# TTAmp_3T0K_amp_tensometer_3.net
KiCad netlist of a schematic drawn in Altium Designer
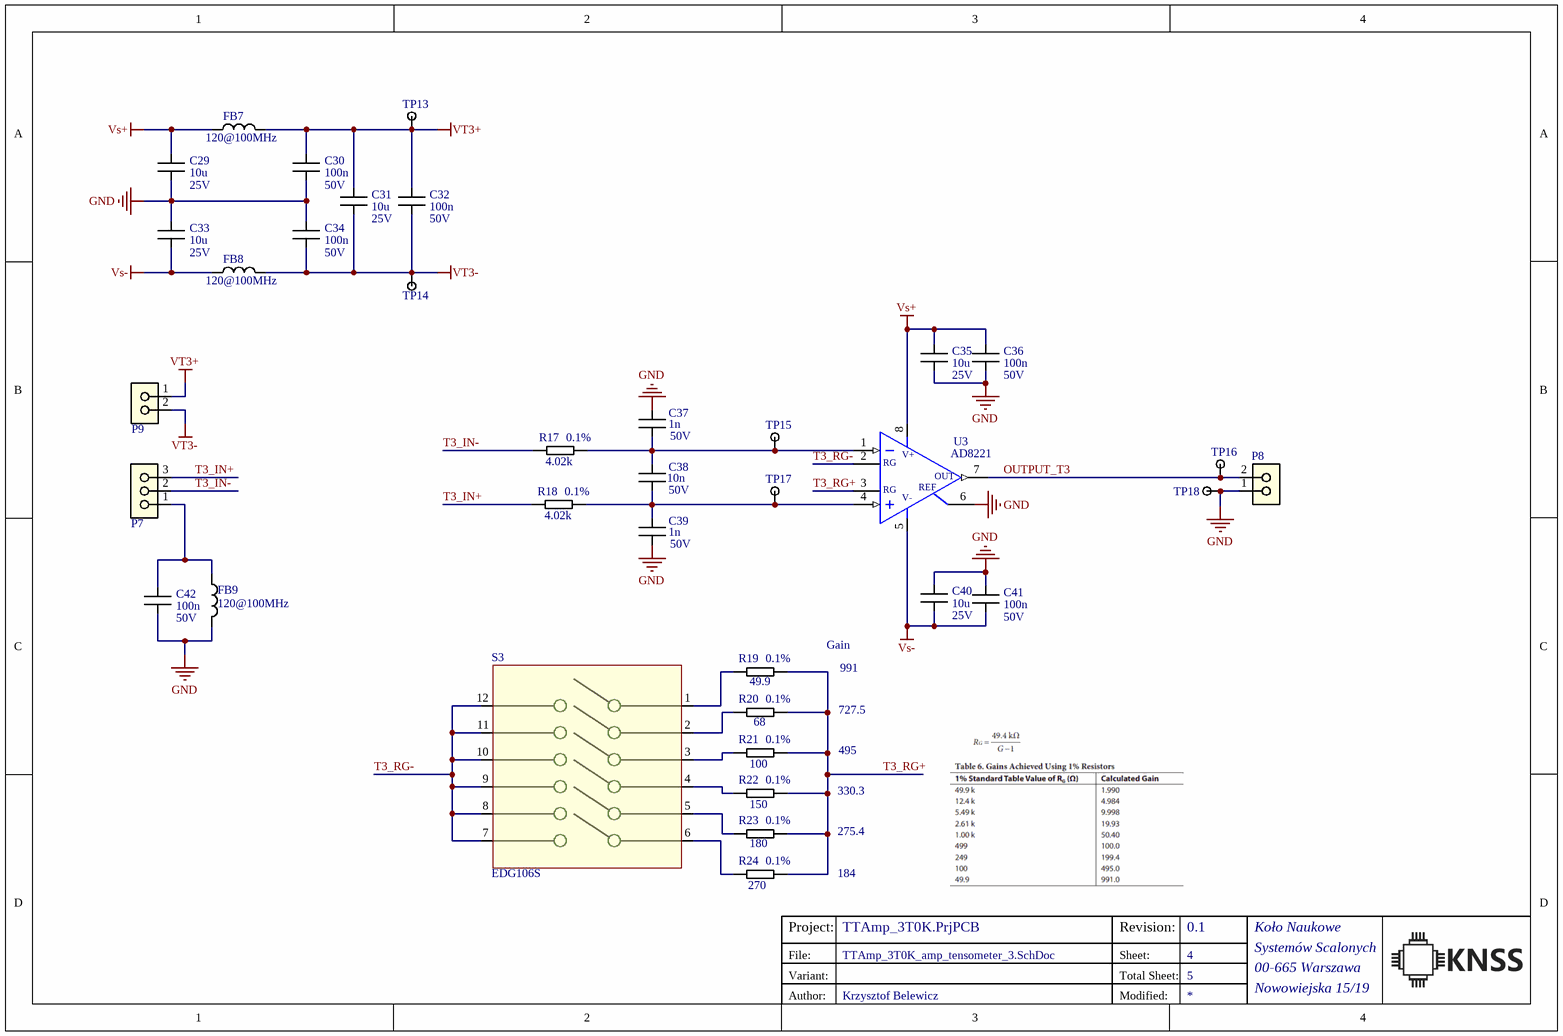
[diagram p0: TTAmp_3T0K_amp_tensometer_3.SchDoc]

(export (version "E")
  (design (tool "Eeschema 10.0.6"))
  (components
    (comp (ref "C29")
      (value "10u")
      (footprint "CAPC2012N")
      (description "Capacitor")
      (fields (field (name "TOLERANCE") "10%") (field (name "MAXVOLTAGE") "25V"))
      (libsource (lib "RLC") (part "Capacitor"))
    )
    (comp (ref "C30")
      (value "100n")
      (footprint "CAPC1608N")
      (description "Capacitor")
      (fields (field (name "TOLERANCE") "10%") (field (name "MAXVOLTAGE") "50V"))
      (libsource (lib "RLC") (part "Capacitor"))
    )
    (comp (ref "C31")
      (value "10u")
      (footprint "CAPC2012N")
      (description "Capacitor")
      (fields (field (name "TOLERANCE") "10%") (field (name "MAXVOLTAGE") "25V"))
      (libsource (lib "RLC") (part "Capacitor"))
    )
    (comp (ref "C32")
      (value "100n")
      (footprint "CAPC1608N")
      (description "Capacitor")
      (fields (field (name "TOLERANCE") "10%") (field (name "MAXVOLTAGE") "50V"))
      (libsource (lib "RLC") (part "Capacitor"))
    )
    (comp (ref "C33")
      (value "10u")
      (footprint "CAPC2012N")
      (description "Capacitor")
      (fields (field (name "TOLERANCE") "10%") (field (name "MAXVOLTAGE") "25V"))
      (libsource (lib "RLC") (part "Capacitor"))
    )
    (comp (ref "C34")
      (value "100n")
      (footprint "CAPC1608N")
      (description "Capacitor")
      (fields (field (name "TOLERANCE") "10%") (field (name "MAXVOLTAGE") "50V"))
      (libsource (lib "RLC") (part "Capacitor"))
    )
    (comp (ref "C35")
      (value "10u")
      (footprint "CAPC2012N")
      (description "Capacitor")
      (fields (field (name "TOLERANCE") "10%") (field (name "MAXVOLTAGE") "25V"))
      (libsource (lib "RLC") (part "Capacitor"))
    )
    (comp (ref "C36")
      (value "100n")
      (footprint "CAPC1608N")
      (description "Capacitor")
      (fields (field (name "TOLERANCE") "10%") (field (name "MAXVOLTAGE") "50V"))
      (libsource (lib "RLC") (part "Capacitor"))
    )
    (comp (ref "C37")
      (value "1n")
      (footprint "CAPC1608N")
      (description "Capacitor")
      (fields (field (name "TOLERANCE") "10%") (field (name "MAXVOLTAGE") "50V"))
      (libsource (lib "RLC") (part "Capacitor"))
    )
    (comp (ref "C38")
      (value "10n")
      (footprint "CAPC1608N")
      (description "Capacitor")
      (fields (field (name "TOLERANCE") "20%") (field (name "MAXVOLTAGE") "50V"))
      (libsource (lib "RLC") (part "Capacitor"))
    )
    (comp (ref "C39")
      (value "1n")
      (footprint "CAPC1608N")
      (description "Capacitor")
      (fields (field (name "TOLERANCE") "10%") (field (name "MAXVOLTAGE") "50V"))
      (libsource (lib "RLC") (part "Capacitor"))
    )
    (comp (ref "C40")
      (value "10u")
      (footprint "CAPC2012N")
      (description "Capacitor")
      (fields (field (name "TOLERANCE") "10%") (field (name "MAXVOLTAGE") "25V"))
      (libsource (lib "RLC") (part "Capacitor"))
    )
    (comp (ref "C41")
      (value "100n")
      (footprint "CAPC1608N")
      (description "Capacitor")
      (fields (field (name "TOLERANCE") "10%") (field (name "MAXVOLTAGE") "50V"))
      (libsource (lib "RLC") (part "Capacitor"))
    )
    (comp (ref "C42")
      (value "100n")
      (footprint "CAPC1608N")
      (description "Capacitor")
      (fields (field (name "TOLERANCE") "10%") (field (name "MAXVOLTAGE") "50V"))
      (libsource (lib "RLC") (part "Capacitor"))
    )
    (comp (ref "FB7")
      (value "120@100MHz")
      (footprint "INDC1608N")
      (description "Ferrite Bead")
      (libsource (lib "") (part "Inductor_1"))
    )
    (comp (ref "FB8")
      (value "120@100MHz")
      (footprint "INDC1608N")
      (description "Ferrite Bead")
      (libsource (lib "") (part "Inductor_1"))
    )
    (comp (ref "FB9")
      (value "120@100MHz")
      (footprint "INDC1608N")
      (description "Ferrite Bead")
      (libsource (lib "RLC") (part "Inductor"))
    )
    (comp (ref "P7")
      (value "AK100/3DS-5,0-V/GRAU")
      (footprint "AK100/3DS-5,0-V/GRAU")
      (description "Listwa zaciskowa do druku; kątowe 90°; 5mm; tory:3; na PCB; 24A")
      (fields (field (name "MANUFACTURER") "PTR MESSTECHNIK"))
      (libsource (lib "Screw Terminals") (part "AK100/3DS-5,0-V/GRAU"))
    )
    (comp (ref "P8")
      (value "AK100/2DS-5,0-V/GRAU")
      (footprint "AK100/2DS-5,0-V/GRAU")
      (description "Listwa zaciskowa do druku; kątowe 90°; 5mm; tory:2; na PCB; 24A")
      (fields (field (name "MANUFACTURER") "PTR MESSTECHNIK"))
      (libsource (lib "Screw Terminals") (part "AK100/2DS-5,0-V/GRAU"))
    )
    (comp (ref "P9")
      (value "AK100/2DS-5,0-V/GRAU")
      (footprint "AK100/2DS-5,0-V/GRAU")
      (description "Listwa zaciskowa do druku; kątowe 90°; 5mm; tory:2; na PCB; 24A")
      (fields (field (name "MANUFACTURER") "PTR MESSTECHNIK"))
      (libsource (lib "") (part "AK100/2DS-5,0-V/GRAU_1"))
    )
    (comp (ref "R17")
      (value "4.02k")
      (footprint "RESC1608N")
      (description "Resistor")
      (fields (field (name "TOLERANCE") "0.1%") (field (name "POWER") "0.1W"))
      (libsource (lib "RLC") (part "Resistor"))
    )
    (comp (ref "R18")
      (value "4.02k")
      (footprint "RESC1608N")
      (description "Resistor")
      (fields (field (name "TOLERANCE") "0.1%") (field (name "POWER") "0.1W"))
      (libsource (lib "RLC") (part "Resistor"))
    )
    (comp (ref "R19")
      (value "49.9")
      (footprint "RESC1608N")
      (description "Resistor")
      (fields (field (name "TOLERANCE") "0.1%") (field (name "POWER") "0.1W"))
      (libsource (lib "RLC") (part "Resistor"))
    )
    (comp (ref "R20")
      (value "68")
      (footprint "RESC1608N")
      (description "Resistor")
      (fields
        (field (name "TOLERANCE") "0.1%")
        (field (name "POWER") "0.1W")
        (field (name "MANUFACTURER") "VIKING")
      )
      (libsource (lib "RLC") (part "Resistor"))
    )
    (comp (ref "R21")
      (value "100")
      (footprint "RESC1608N")
      (description "Resistor")
      (fields (field (name "TOLERANCE") "0.1%") (field (name "POWER") "0.1W"))
      (libsource (lib "RLC") (part "Resistor"))
    )
    (comp (ref "R22")
      (value "150")
      (footprint "RESC1608N")
      (description "Resistor")
      (fields (field (name "TOLERANCE") "0.1%") (field (name "POWER") "0.1W"))
      (libsource (lib "RLC") (part "Resistor"))
    )
    (comp (ref "R23")
      (value "180")
      (footprint "RESC1608N")
      (description "Resistor")
      (fields (field (name "TOLERANCE") "0.1%") (field (name "POWER") "0.1W"))
      (libsource (lib "RLC") (part "Resistor"))
    )
    (comp (ref "R24")
      (value "270")
      (footprint "RESC1608N")
      (description "Resistor")
      (fields (field (name "TOLERANCE") "0.1%") (field (name "POWER") "0.1W"))
      (libsource (lib "RLC") (part "Resistor"))
    )
    (comp (ref "S3")
      (value "EDG106S")
      (footprint "EDG106S")
      (description "Przełącznik: DIP-SWITCH; Ilość sekcji:6; ON-OFF; 0,1A/24VDC; 500V")
      (libsource (lib "ECE") (part "EDG106S"))
    )
    (comp (ref "TP13")
      (value "~")
      (footprint "TP-SMD-1.0MM")
      (description "Test Point for probe")
      (libsource (lib "TestPoints") (part "TP1"))
    )
    (comp (ref "TP14")
      (value "~")
      (footprint "TP-SMD-1.0MM")
      (description "Test Point for probe")
      (libsource (lib "TestPoints") (part "TP1"))
    )
    (comp (ref "TP15")
      (value "~")
      (footprint "TP-SMD-1.0MM")
      (description "Test Point for probe")
      (libsource (lib "TestPoints") (part "TP1"))
    )
    (comp (ref "TP16")
      (value "~")
      (footprint "TP-SMD-1.0MM")
      (description "Test Point for probe")
      (libsource (lib "TestPoints") (part "TP1"))
    )
    (comp (ref "TP17")
      (value "~")
      (footprint "TP-SMD-1.0MM")
      (description "Test Point for probe")
      (libsource (lib "TestPoints") (part "TP1"))
    )
    (comp (ref "TP18")
      (value "~")
      (footprint "TP-SMD-1.0MM")
      (description "Test Point for probe")
      (libsource (lib "TestPoints") (part "TP1"))
    )
    (comp (ref "U3")
      (value "AD8221")
      (footprint "R-8_N")
      (description "Precision Instrumentation Amplifier")
      (libsource (lib "AD Instrumentation Amplifier") (part "AD8221"))
    )
  )
  (nets
    (net (code "1") (name "/OUTPUT_T3") (class "Default")
      (node (ref "P8") (pin "2") (pinfunction "2_2") (pintype "passive"))
      (node (ref "TP16") (pin "1") (pinfunction "1_1") (pintype "passive"))
      (node (ref "U3") (pin "7") (pinfunction "OUT_7") (pintype "output"))
    )
    (net (code "2") (name "/T3_IN+") (class "Default")
      (node (ref "P7") (pin "3") (pinfunction "3_3") (pintype "passive"))
      (node (ref "R18") (pin "2") (pinfunction "2_2") (pintype "passive"))
    )
    (net (code "3") (name "/T3_IN-") (class "Default")
      (node (ref "P7") (pin "2") (pinfunction "2_2") (pintype "passive"))
      (node (ref "R17") (pin "2") (pinfunction "2_2") (pintype "passive"))
    )
    (net (code "4") (name "/T3_RG+") (class "Default")
      (node (ref "R19") (pin "1") (pinfunction "1_1") (pintype "passive"))
      (node (ref "R20") (pin "1") (pinfunction "1_1") (pintype "passive"))
      (node (ref "R21") (pin "1") (pinfunction "1_1") (pintype "passive"))
      (node (ref "R22") (pin "1") (pinfunction "1_1") (pintype "passive"))
      (node (ref "R23") (pin "1") (pinfunction "1_1") (pintype "passive"))
      (node (ref "R24") (pin "1") (pinfunction "1_1") (pintype "passive"))
      (node (ref "U3") (pin "3") (pinfunction "RG_3") (pintype "passive"))
    )
    (net (code "5") (name "/T3_RG-") (class "Default")
      (node (ref "S3") (pin "10") (pinfunction "10_10") (pintype "passive"))
      (node (ref "S3") (pin "11") (pinfunction "11_11") (pintype "passive"))
      (node (ref "S3") (pin "12") (pinfunction "12_12") (pintype "passive"))
      (node (ref "S3") (pin "7") (pinfunction "13_7") (pintype "passive"))
      (node (ref "S3") (pin "8") (pinfunction "12_8") (pintype "passive"))
      (node (ref "S3") (pin "9") (pinfunction "11_9") (pintype "passive"))
      (node (ref "U3") (pin "2") (pinfunction "RG_2") (pintype "passive"))
    )
    (net (code "6") (name "GND") (class "Default")
      (node (ref "C29") (pin "1") (pinfunction "1_1") (pintype "passive"))
      (node (ref "C30") (pin "1") (pinfunction "1_1") (pintype "passive"))
      (node (ref "C33") (pin "2") (pinfunction "2_2") (pintype "passive"))
      (node (ref "C34") (pin "2") (pinfunction "2_2") (pintype "passive"))
      (node (ref "C35") (pin "1") (pinfunction "1_1") (pintype "passive"))
      (node (ref "C36") (pin "1") (pinfunction "1_1") (pintype "passive"))
      (node (ref "C37") (pin "2") (pinfunction "2_2") (pintype "passive"))
      (node (ref "C39") (pin "1") (pinfunction "1_1") (pintype "passive"))
      (node (ref "C40") (pin "2") (pinfunction "2_2") (pintype "passive"))
      (node (ref "C41") (pin "2") (pinfunction "2_2") (pintype "passive"))
      (node (ref "C42") (pin "1") (pinfunction "1_1") (pintype "passive"))
      (node (ref "FB9") (pin "2") (pinfunction "2_2") (pintype "passive"))
      (node (ref "P8") (pin "1") (pinfunction "1_1") (pintype "passive"))
      (node (ref "TP18") (pin "1") (pinfunction "1_1") (pintype "passive"))
      (node (ref "U3") (pin "6") (pinfunction "REF_6") (pintype "passive"))
    )
    (net (code "7") (name "Net-(C42-Pad2)") (class "Default")
      (node (ref "C42") (pin "2") (pinfunction "2_2") (pintype "passive"))
      (node (ref "FB9") (pin "1") (pinfunction "1_1") (pintype "passive"))
      (node (ref "P7") (pin "1") (pinfunction "1_1") (pintype "passive"))
    )
    (net (code "8") (name "Net-(R19-Pad2)") (class "Default")
      (node (ref "R19") (pin "2") (pinfunction "2_2") (pintype "passive"))
      (node (ref "S3") (pin "1") (pinfunction "1_1") (pintype "passive"))
    )
    (net (code "9") (name "Net-(R20-Pad2)") (class "Default")
      (node (ref "R20") (pin "2") (pinfunction "2_2") (pintype "passive"))
      (node (ref "S3") (pin "2") (pinfunction "2_2") (pintype "passive"))
    )
    (net (code "10") (name "Net-(R21-Pad2)") (class "Default")
      (node (ref "R21") (pin "2") (pinfunction "2_2") (pintype "passive"))
      (node (ref "S3") (pin "3") (pinfunction "3_3") (pintype "passive"))
    )
    (net (code "11") (name "Net-(R22-Pad2)") (class "Default")
      (node (ref "R22") (pin "2") (pinfunction "2_2") (pintype "passive"))
      (node (ref "S3") (pin "4") (pinfunction "4_4") (pintype "passive"))
    )
    (net (code "12") (name "Net-(R23-Pad2)") (class "Default")
      (node (ref "R23") (pin "2") (pinfunction "2_2") (pintype "passive"))
      (node (ref "S3") (pin "5") (pinfunction "5_5") (pintype "passive"))
    )
    (net (code "13") (name "Net-(R24-Pad2)") (class "Default")
      (node (ref "R24") (pin "2") (pinfunction "2_2") (pintype "passive"))
      (node (ref "S3") (pin "6") (pinfunction "6_6") (pintype "passive"))
    )
    (net (code "14") (name "Net-(U3-+IN)") (class "Default")
      (node (ref "C38") (pin "1") (pinfunction "1_1") (pintype "passive"))
      (node (ref "C39") (pin "2") (pinfunction "2_2") (pintype "passive"))
      (node (ref "R18") (pin "1") (pinfunction "1_1") (pintype "passive"))
      (node (ref "TP17") (pin "1") (pinfunction "1_1") (pintype "passive"))
      (node (ref "U3") (pin "4") (pinfunction "+IN_4") (pintype "input"))
    )
    (net (code "15") (name "Net-(U3--IN)") (class "Default")
      (node (ref "C37") (pin "1") (pinfunction "1_1") (pintype "passive"))
      (node (ref "C38") (pin "2") (pinfunction "2_2") (pintype "passive"))
      (node (ref "R17") (pin "1") (pinfunction "1_1") (pintype "passive"))
      (node (ref "TP15") (pin "1") (pinfunction "1_1") (pintype "passive"))
      (node (ref "U3") (pin "1") (pinfunction "-IN_1") (pintype "input"))
    )
    (net (code "16") (name "VT3+") (class "Default")
      (node (ref "C30") (pin "2") (pinfunction "2_2") (pintype "passive"))
      (node (ref "C31") (pin "2") (pinfunction "2_2") (pintype "passive"))
      (node (ref "C32") (pin "2") (pinfunction "2_2") (pintype "passive"))
      (node (ref "FB7") (pin "1") (pinfunction "1_1") (pintype "passive"))
      (node (ref "P9") (pin "1") (pinfunction "1_1") (pintype "passive"))
      (node (ref "TP13") (pin "1") (pinfunction "1_1") (pintype "passive"))
    )
    (net (code "17") (name "VT3-") (class "Default")
      (node (ref "C31") (pin "1") (pinfunction "1_1") (pintype "passive"))
      (node (ref "C32") (pin "1") (pinfunction "1_1") (pintype "passive"))
      (node (ref "C34") (pin "1") (pinfunction "1_1") (pintype "passive"))
      (node (ref "FB8") (pin "1") (pinfunction "1_1") (pintype "passive"))
      (node (ref "P9") (pin "2") (pinfunction "2_2") (pintype "passive"))
      (node (ref "TP14") (pin "1") (pinfunction "1_1") (pintype "passive"))
    )
    (net (code "18") (name "Vs+") (class "Default")
      (node (ref "C29") (pin "2") (pinfunction "2_2") (pintype "passive"))
      (node (ref "C35") (pin "2") (pinfunction "2_2") (pintype "passive"))
      (node (ref "C36") (pin "2") (pinfunction "2_2") (pintype "passive"))
      (node (ref "FB7") (pin "2") (pinfunction "2_2") (pintype "passive"))
      (node (ref "U3") (pin "8") (pinfunction "V+_8") (pintype "power_in"))
    )
    (net (code "19") (name "Vs-") (class "Default")
      (node (ref "C33") (pin "1") (pinfunction "1_1") (pintype "passive"))
      (node (ref "C40") (pin "1") (pinfunction "1_1") (pintype "passive"))
      (node (ref "C41") (pin "1") (pinfunction "1_1") (pintype "passive"))
      (node (ref "FB8") (pin "2") (pinfunction "2_2") (pintype "passive"))
      (node (ref "U3") (pin "5") (pinfunction "V-_5") (pintype "power_in"))
    )
  )
)
